# ADJ_REG.net
KiCad netlist of a schematic drawn in Altium Designer
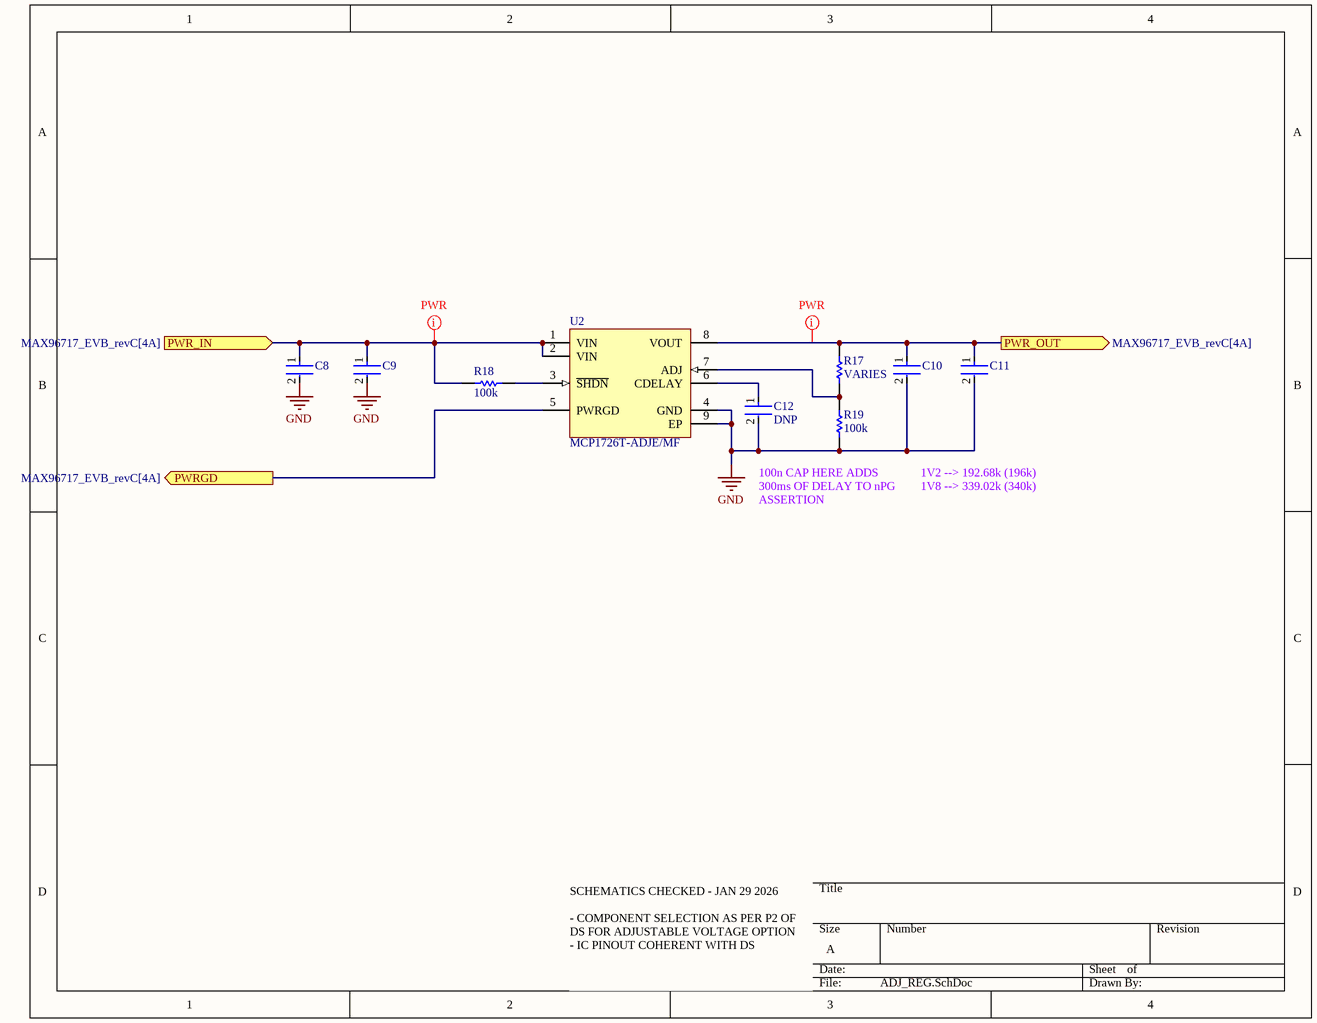
[diagram p0: ADJ_REG.SchDoc]

(export (version "E")
  (design (tool "Eeschema 10.0.6"))
  (components
    (comp (ref "C8")
      (value "C0805C475J4RACAUTO")
      (footprint "FP-C0805C475J4RACAUTO-MFG")
      (description "C0805C475J4RACAUTO Cap Ceramic 4.7uF 16V X7R 5% Pad SMD 0805 125C Automotive T/R")
      (fields (field (name "TOLERANCE") "5%"))
      (libsource (lib "Altium Content Vault") (part "b4654b650e69147ec39a6b967a45e02"))
    )
    (comp (ref "C9")
      (value "DNP")
      (footprint "FP-C0805C475J4RACAUTO-MFG")
      (description "C0805C475J4RACAUTO Cap Ceramic 4.7uF 16V X7R 5% Pad SMD 0805 125C Automotive T/R")
      (fields (field (name "TOLERANCE") "5%"))
      (libsource (lib "Altium Content Vault") (part "b4654b650e69147ec39a6b967a45e02"))
    )
    (comp (ref "C10")
      (value "HMK325B7105KN-T")
      (footprint "FP-1210-L_3_2_0_3-W_2_5_0-IPC_B")
      (description "None")
      (fields (field (name "TOLERANCE") "10%") (field (name "VOLTAGE") "100V"))
      (libsource (lib "Altium Content Vault") (part "02cd4be3c70576c341d710602a673aa"))
    )
    (comp (ref "C11")
      (value "DNP")
      (footprint "FP-1210-L_3_2_0_3-W_2_5_0-IPC_B")
      (description "None")
      (fields (field (name "TOLERANCE") "10%") (field (name "VOLTAGE") "100V"))
      (libsource (lib "Altium Content Vault") (part "02cd4be3c70576c341d710602a673aa"))
    )
    (comp (ref "C12")
      (value "DNP")
      (footprint "FP-0402-L_1_0_0_05-W_0_5-IPC_A")
      (description "LARGE PADS, 0402 CAP, CHANGE COMMENT TO MATCH REAL P/N")
      (libsource (lib "Space Concordia") (part "b4654b650e69147ec39a6b967a45e02"))
    )
    (comp (ref "R17")
      (value "VARIES")
      (footprint "R0603B")
      (description "Resistor")
      (libsource (lib "Space Concordia") (part "Resistor"))
    )
    (comp (ref "R18")
      (value "100k")
      (footprint "R0603B")
      (description "Resistor")
      (libsource (lib "Space Concordia") (part "Resistor"))
    )
    (comp (ref "R19")
      (value "100k")
      (footprint "R0603B")
      (description "Resistor")
      (libsource (lib "Space Concordia") (part "Resistor"))
    )
    (comp (ref "U2")
      (value "MCP1726T-ADJE/MF")
      (footprint "DFN-MF8")
      (libsource (lib "Altium Content Vault") (part "PM-LINEREG-MCP1726-IL9A"))
    )
  )
  (nets
    (net (code "1") (name "/PWRGD") (class "Default")
      (node (ref "U2") (pin "5") (pinfunction "PWRGD_5") (pintype "power_in"))
    )
    (net (code "2") (name "/PWR_IN") (class "Default")
      (node (ref "C8") (pin "1") (pinfunction "1_1") (pintype "passive"))
      (node (ref "C9") (pin "1") (pinfunction "1_1") (pintype "passive"))
      (node (ref "R18") (pin "1") (pinfunction "1_1") (pintype "passive"))
      (node (ref "U2") (pin "1") (pinfunction "VIN_1") (pintype "power_in"))
      (node (ref "U2") (pin "2") (pinfunction "VIN_2") (pintype "power_in"))
    )
    (net (code "3") (name "/PWR_OUT") (class "Default")
      (node (ref "C10") (pin "1") (pinfunction "1_1") (pintype "passive"))
      (node (ref "C11") (pin "1") (pinfunction "1_1") (pintype "passive"))
      (node (ref "R17") (pin "2") (pinfunction "2_2") (pintype "passive"))
      (node (ref "U2") (pin "8") (pinfunction "VOUT_8") (pintype "power_in"))
    )
    (net (code "4") (name "GND") (class "Default")
      (node (ref "C10") (pin "2") (pinfunction "2_2") (pintype "passive"))
      (node (ref "C11") (pin "2") (pinfunction "2_2") (pintype "passive"))
      (node (ref "C12") (pin "2") (pinfunction "2_2") (pintype "passive"))
      (node (ref "C8") (pin "2") (pinfunction "2_2") (pintype "passive"))
      (node (ref "C9") (pin "2") (pinfunction "2_2") (pintype "passive"))
      (node (ref "R19") (pin "1") (pinfunction "1_1") (pintype "passive"))
      (node (ref "U2") (pin "4") (pinfunction "GND_4") (pintype "power_in"))
      (node (ref "U2") (pin "9") (pinfunction "EP_9") (pintype "power_in"))
    )
    (net (code "5") (name "Net-(U2-ADJ)") (class "Default")
      (node (ref "R17") (pin "1") (pinfunction "1_1") (pintype "passive"))
      (node (ref "R19") (pin "2") (pinfunction "2_2") (pintype "passive"))
      (node (ref "U2") (pin "7") (pinfunction "ADJ_7") (pintype "input"))
    )
    (net (code "6") (name "Net-(U2-CDELAY)") (class "Default")
      (node (ref "C12") (pin "1") (pinfunction "1_1") (pintype "passive"))
      (node (ref "U2") (pin "6") (pinfunction "CDELAY_6") (pintype "passive"))
    )
    (net (code "7") (name "Net-(U2-~{SHDN})") (class "Default")
      (node (ref "R18") (pin "2") (pinfunction "2_2") (pintype "passive"))
      (node (ref "U2") (pin "3") (pinfunction "~{SHDN}_3") (pintype "input"))
    )
  )
)
